# Base_Board.net
KiCad netlist of a schematic drawn in EAGLE
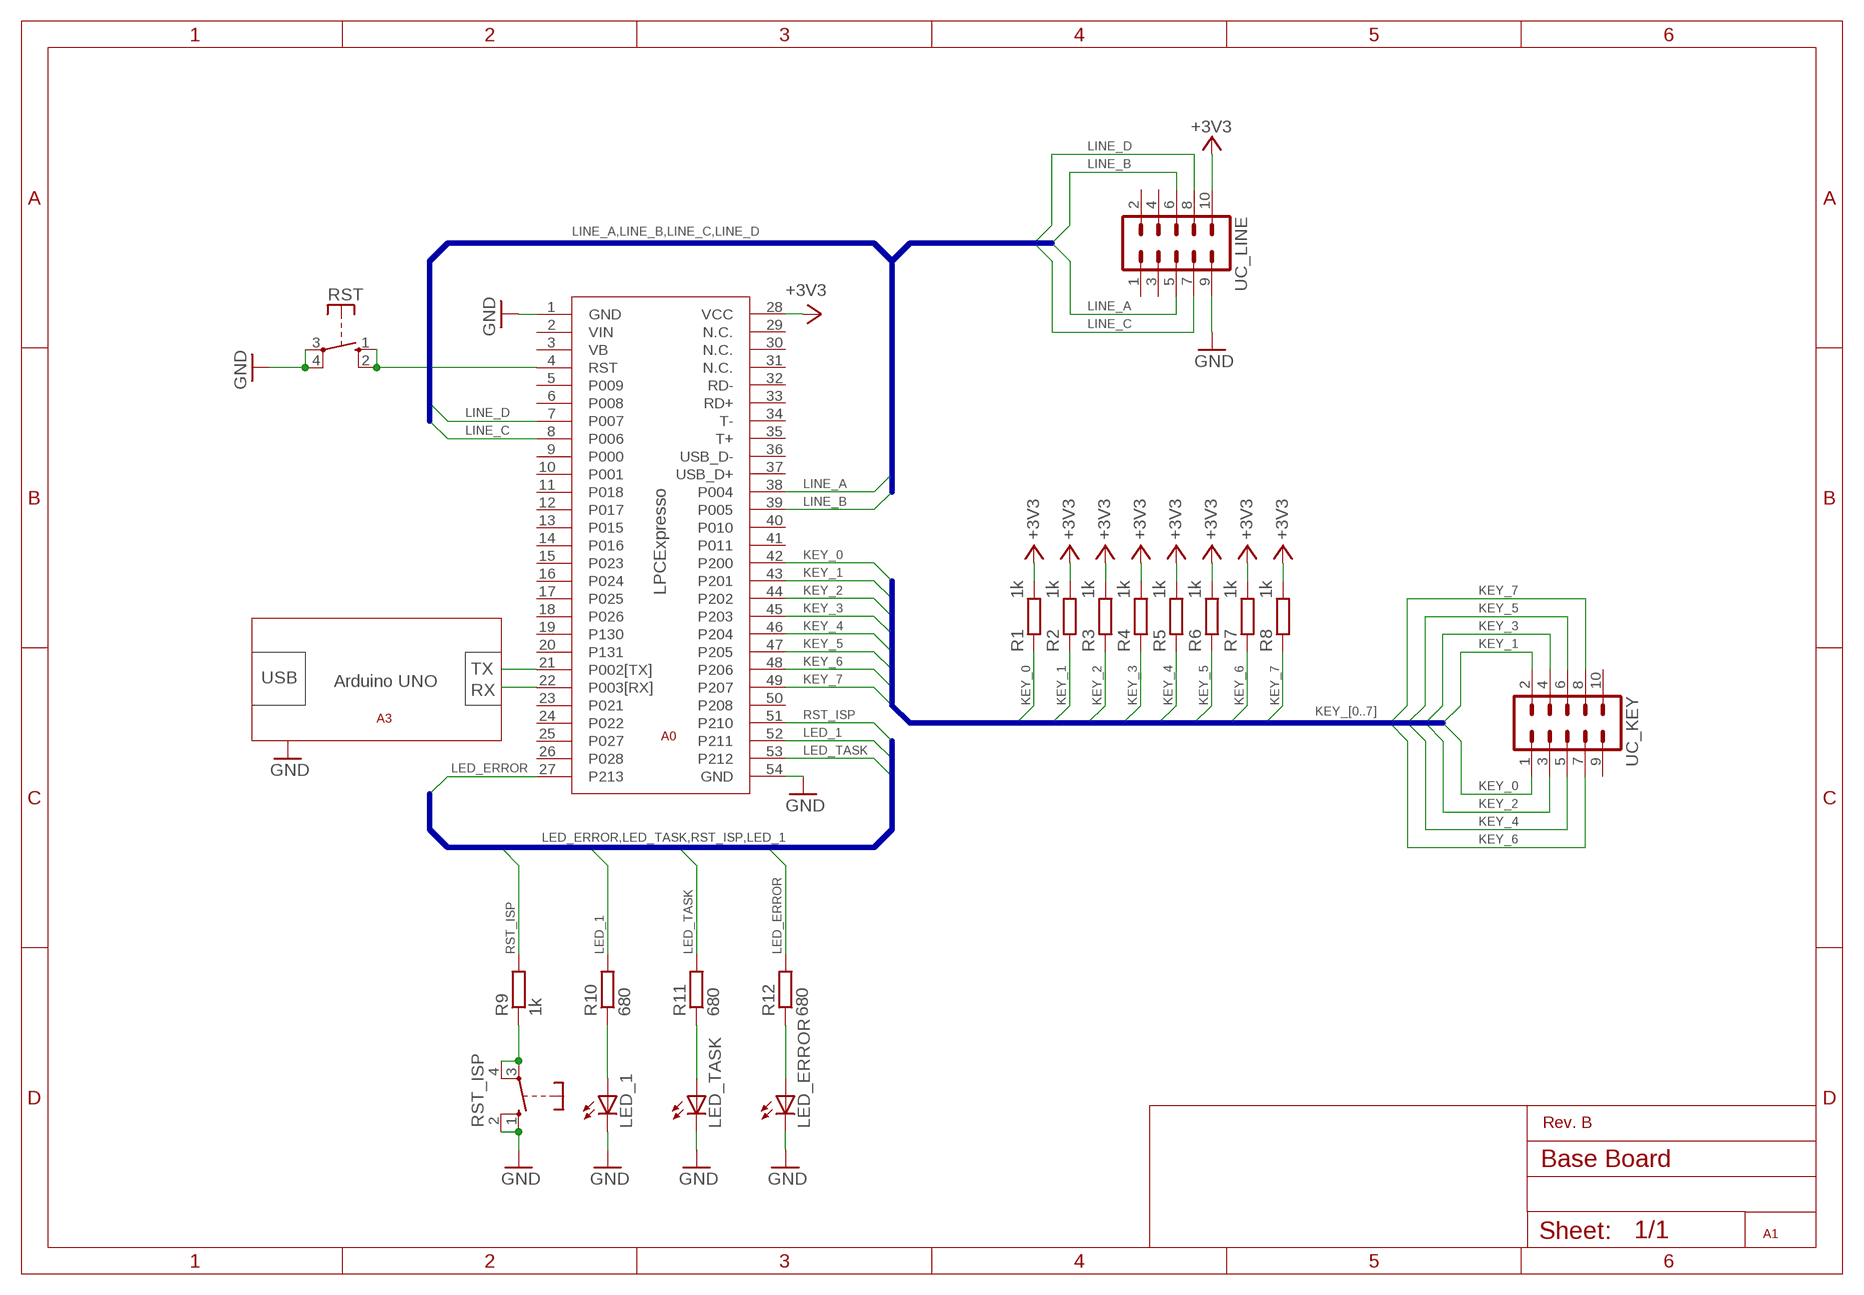
[diagram p0: schematic, sheet 1]

(export (version "E")
  (design (tool "Eeschema 10.0.6"))
  (components
    (comp (ref "LED_1")
      (value "LED5MM")
      (footprint "eagle-import:LED5MM")
      (libsource (lib "eagle-import") (part "LED5MM"))
    )
    (comp (ref "LED_ERROR")
      (value "LED5MM")
      (footprint "eagle-import:LED5MM")
      (libsource (lib "eagle-import") (part "LED5MM"))
    )
    (comp (ref "LED_TASK")
      (value "LED5MM")
      (footprint "eagle-import:LED5MM")
      (libsource (lib "eagle-import") (part "LED5MM"))
    )
    (comp (ref "R1")
      (value "1k")
      (footprint "eagle-import:0204_5")
      (libsource (lib "eagle-import") (part "R-EU_0204/5"))
    )
    (comp (ref "R2")
      (value "1k")
      (footprint "eagle-import:0204_5")
      (libsource (lib "eagle-import") (part "R-EU_0204/5"))
    )
    (comp (ref "R3")
      (value "1k")
      (footprint "eagle-import:0204_5")
      (libsource (lib "eagle-import") (part "R-EU_0204/5"))
    )
    (comp (ref "R4")
      (value "1k")
      (footprint "eagle-import:0204_5")
      (libsource (lib "eagle-import") (part "R-EU_0204/5"))
    )
    (comp (ref "R5")
      (value "1k")
      (footprint "eagle-import:0204_5")
      (libsource (lib "eagle-import") (part "R-EU_0204/5"))
    )
    (comp (ref "R6")
      (value "1k")
      (footprint "eagle-import:0204_5")
      (libsource (lib "eagle-import") (part "R-EU_0204/5"))
    )
    (comp (ref "R7")
      (value "1k")
      (footprint "eagle-import:0204_5")
      (libsource (lib "eagle-import") (part "R-EU_0204/5"))
    )
    (comp (ref "R8")
      (value "1k")
      (footprint "eagle-import:0204_5")
      (libsource (lib "eagle-import") (part "R-EU_0204/5"))
    )
    (comp (ref "R9")
      (value "1k")
      (footprint "eagle-import:0204_5")
      (libsource (lib "eagle-import") (part "R-EU_0204/5"))
    )
    (comp (ref "R10")
      (value "680")
      (footprint "eagle-import:0204_5")
      (libsource (lib "eagle-import") (part "R-EU_0204/5"))
    )
    (comp (ref "R11")
      (value "680")
      (footprint "eagle-import:0204_5")
      (libsource (lib "eagle-import") (part "R-EU_0204/5"))
    )
    (comp (ref "R12")
      (value "680")
      (footprint "eagle-import:0204_5")
      (libsource (lib "eagle-import") (part "R-EU_0204/5"))
    )
    (comp (ref "RST")
      (value "DT6")
      (footprint "eagle-import:DT6")
      (libsource (lib "eagle-import") (part "DT6"))
    )
    (comp (ref "RST_ISP")
      (value "DT6")
      (footprint "eagle-import:DT6")
      (libsource (lib "eagle-import") (part "DT6"))
    )
    (comp (ref "U$1")
      (value "LPCEXPRESSO")
      (footprint "eagle-import:LPCEXPRESSO")
      (libsource (lib "eagle-import") (part "LPCEXPRESSO"))
    )
    (comp (ref "UC_KEY")
      (value "ML10")
      (footprint "eagle-import:ML10")
      (libsource (lib "eagle-import") (part "ML10"))
    )
    (comp (ref "UC_LINE")
      (value "ML10")
      (footprint "eagle-import:ML10")
      (libsource (lib "eagle-import") (part "ML10"))
    )
  )
  (nets
    (net (code "1") (name "+3V3") (class "Default")
      (node (ref "R1") (pin "1") (pinfunction "1_1") (pintype "passive"))
      (node (ref "R2") (pin "1") (pinfunction "1_1") (pintype "passive"))
      (node (ref "R3") (pin "1") (pinfunction "1_1") (pintype "passive"))
      (node (ref "R4") (pin "1") (pinfunction "1_1") (pintype "passive"))
      (node (ref "R5") (pin "1") (pinfunction "1_1") (pintype "passive"))
      (node (ref "R6") (pin "1") (pinfunction "1_1") (pintype "passive"))
      (node (ref "R7") (pin "1") (pinfunction "1_1") (pintype "passive"))
      (node (ref "R8") (pin "1") (pinfunction "1_1") (pintype "passive"))
      (node (ref "U$1") (pin "28") (pinfunction "VCC_28") (pintype "power_in"))
      (node (ref "UC_LINE") (pin "10") (pinfunction "10_10") (pintype "passive"))
    )
    (net (code "2") (name "/KEY_0") (class "Default")
      (node (ref "R1") (pin "2") (pinfunction "2_2") (pintype "passive"))
      (node (ref "U$1") (pin "42") (pinfunction "P200_42") (pintype "bidirectional"))
      (node (ref "UC_KEY") (pin "1") (pinfunction "1_1") (pintype "passive"))
    )
    (net (code "3") (name "/KEY_1") (class "Default")
      (node (ref "R2") (pin "2") (pinfunction "2_2") (pintype "passive"))
      (node (ref "U$1") (pin "43") (pinfunction "P201_43") (pintype "bidirectional"))
      (node (ref "UC_KEY") (pin "2") (pinfunction "2_2") (pintype "passive"))
    )
    (net (code "4") (name "/KEY_2") (class "Default")
      (node (ref "R3") (pin "2") (pinfunction "2_2") (pintype "passive"))
      (node (ref "U$1") (pin "44") (pinfunction "P202_44") (pintype "bidirectional"))
      (node (ref "UC_KEY") (pin "3") (pinfunction "3_3") (pintype "passive"))
    )
    (net (code "5") (name "/KEY_3") (class "Default")
      (node (ref "R4") (pin "2") (pinfunction "2_2") (pintype "passive"))
      (node (ref "U$1") (pin "45") (pinfunction "P203_45") (pintype "bidirectional"))
      (node (ref "UC_KEY") (pin "4") (pinfunction "4_4") (pintype "passive"))
    )
    (net (code "6") (name "/KEY_4") (class "Default")
      (node (ref "R5") (pin "2") (pinfunction "2_2") (pintype "passive"))
      (node (ref "U$1") (pin "46") (pinfunction "P204_46") (pintype "bidirectional"))
      (node (ref "UC_KEY") (pin "5") (pinfunction "5_5") (pintype "passive"))
    )
    (net (code "7") (name "/KEY_5") (class "Default")
      (node (ref "R6") (pin "2") (pinfunction "2_2") (pintype "passive"))
      (node (ref "U$1") (pin "47") (pinfunction "P205_47") (pintype "bidirectional"))
      (node (ref "UC_KEY") (pin "6") (pinfunction "6_6") (pintype "passive"))
    )
    (net (code "8") (name "/KEY_6") (class "Default")
      (node (ref "R7") (pin "2") (pinfunction "2_2") (pintype "passive"))
      (node (ref "U$1") (pin "48") (pinfunction "P206_48") (pintype "bidirectional"))
      (node (ref "UC_KEY") (pin "7") (pinfunction "7_7") (pintype "passive"))
    )
    (net (code "9") (name "/KEY_7") (class "Default")
      (node (ref "R8") (pin "2") (pinfunction "2_2") (pintype "passive"))
      (node (ref "U$1") (pin "49") (pinfunction "P207_49") (pintype "bidirectional"))
      (node (ref "UC_KEY") (pin "8") (pinfunction "8_8") (pintype "passive"))
    )
    (net (code "11") (name "/LED_1") (class "Default")
      (node (ref "R10") (pin "2") (pinfunction "2_2") (pintype "passive"))
      (node (ref "U$1") (pin "52") (pinfunction "P211_52") (pintype "bidirectional"))
    )
    (net (code "12") (name "/LED_ERROR") (class "Default")
      (node (ref "R12") (pin "2") (pinfunction "2_2") (pintype "passive"))
      (node (ref "U$1") (pin "27") (pinfunction "P213_27") (pintype "bidirectional"))
    )
    (net (code "13") (name "/LED_TASK") (class "Default")
      (node (ref "R11") (pin "2") (pinfunction "2_2") (pintype "passive"))
      (node (ref "U$1") (pin "53") (pinfunction "P212_53") (pintype "bidirectional"))
    )
    (net (code "14") (name "/LINE_A") (class "Default")
      (node (ref "U$1") (pin "38") (pinfunction "P004_38") (pintype "bidirectional"))
      (node (ref "UC_LINE") (pin "5") (pinfunction "5_5") (pintype "passive"))
    )
    (net (code "15") (name "/LINE_B") (class "Default")
      (node (ref "U$1") (pin "39") (pinfunction "P005_39") (pintype "bidirectional"))
      (node (ref "UC_LINE") (pin "6") (pinfunction "6_6") (pintype "passive"))
    )
    (net (code "16") (name "/LINE_C") (class "Default")
      (node (ref "U$1") (pin "8") (pinfunction "P006_8") (pintype "bidirectional"))
      (node (ref "UC_LINE") (pin "7") (pinfunction "7_7") (pintype "passive"))
    )
    (net (code "17") (name "/LINE_D") (class "Default")
      (node (ref "U$1") (pin "7") (pinfunction "P007_7") (pintype "bidirectional"))
      (node (ref "UC_LINE") (pin "8") (pinfunction "8_8") (pintype "passive"))
    )
    (net (code "18") (name "/RST_ISP") (class "Default")
      (node (ref "R9") (pin "2") (pinfunction "2_2") (pintype "passive"))
      (node (ref "U$1") (pin "51") (pinfunction "P210_51") (pintype "bidirectional"))
    )
    (net (code "19") (name "/VB") (class "Default")
      (node (ref "U$1") (pin "3") (pinfunction "VB_3") (pintype "power_in"))
    )
    (net (code "22") (name "GND") (class "Default")
      (node (ref "LED_1") (pin "K") (pinfunction "C_K") (pintype "passive"))
      (node (ref "LED_ERROR") (pin "K") (pinfunction "C_K") (pintype "passive"))
      (node (ref "LED_TASK") (pin "K") (pinfunction "C_K") (pintype "passive"))
      (node (ref "RST") (pin "3") (pinfunction "P_3") (pintype "passive"))
      (node (ref "RST") (pin "4") (pinfunction "P_4") (pintype "passive"))
      (node (ref "RST_ISP") (pin "1") (pinfunction "S_1") (pintype "passive"))
      (node (ref "RST_ISP") (pin "2") (pinfunction "S_2") (pintype "passive"))
      (node (ref "U$1") (pin "1") (pinfunction "GND_1") (pintype "power_in"))
      (node (ref "U$1") (pin "54") (pinfunction "GND_54") (pintype "power_in"))
      (node (ref "UC_LINE") (pin "9") (pinfunction "9_9") (pintype "passive"))
    )
    (net (code "23") (name "Net-(LED_1-PadA)") (class "Default")
      (node (ref "LED_1") (pin "A") (pinfunction "A_A") (pintype "passive"))
      (node (ref "R10") (pin "1") (pinfunction "1_1") (pintype "passive"))
    )
    (net (code "24") (name "Net-(LED_ERROR-PadA)") (class "Default")
      (node (ref "LED_ERROR") (pin "A") (pinfunction "A_A") (pintype "passive"))
      (node (ref "R12") (pin "1") (pinfunction "1_1") (pintype "passive"))
    )
    (net (code "25") (name "Net-(LED_TASK-PadA)") (class "Default")
      (node (ref "LED_TASK") (pin "A") (pinfunction "A_A") (pintype "passive"))
      (node (ref "R11") (pin "1") (pinfunction "1_1") (pintype "passive"))
    )
    (net (code "26") (name "Net-(R9-Pad1)") (class "Default")
      (node (ref "R9") (pin "1") (pinfunction "1_1") (pintype "passive"))
      (node (ref "RST_ISP") (pin "3") (pinfunction "P_3") (pintype "passive"))
      (node (ref "RST_ISP") (pin "4") (pinfunction "P_4") (pintype "passive"))
    )
    (net (code "27") (name "Net-(U$1-RST)") (class "Default")
      (node (ref "RST") (pin "1") (pinfunction "S_1") (pintype "passive"))
      (node (ref "RST") (pin "2") (pinfunction "S_2") (pintype "passive"))
      (node (ref "U$1") (pin "4") (pinfunction "RST_4") (pintype "bidirectional"))
    )
    (net (code "28") (name "unconnected-(U$1-N.C.-Pad29)") (class "Default")
      (node (ref "U$1") (pin "29") (pinfunction "N.C._29") (pintype "no_connect"))
    )
    (net (code "29") (name "unconnected-(U$1-N.C.-Pad30)") (class "Default")
      (node (ref "U$1") (pin "30") (pinfunction "N.C._30") (pintype "no_connect"))
    )
    (net (code "30") (name "unconnected-(U$1-N.C.-Pad31)") (class "Default")
      (node (ref "U$1") (pin "31") (pinfunction "N.C._31") (pintype "no_connect"))
    )
    (net (code "31") (name "unconnected-(U$1-P000-Pad9)") (class "Default")
      (node (ref "U$1") (pin "9") (pinfunction "P000_9") (pintype "bidirectional"))
    )
    (net (code "32") (name "unconnected-(U$1-P001-Pad10)") (class "Default")
      (node (ref "U$1") (pin "10") (pinfunction "P001_10") (pintype "bidirectional"))
    )
    (net (code "33") (name "unconnected-(U$1-P002[TX]-Pad21)") (class "Default")
      (node (ref "U$1") (pin "21") (pinfunction "P002[TX]_21") (pintype "bidirectional"))
    )
    (net (code "34") (name "unconnected-(U$1-P003[RX]-Pad22)") (class "Default")
      (node (ref "U$1") (pin "22") (pinfunction "P003[RX]_22") (pintype "bidirectional"))
    )
    (net (code "35") (name "unconnected-(U$1-P008-Pad6)") (class "Default")
      (node (ref "U$1") (pin "6") (pinfunction "P008_6") (pintype "bidirectional"))
    )
    (net (code "36") (name "unconnected-(U$1-P009-Pad5)") (class "Default")
      (node (ref "U$1") (pin "5") (pinfunction "P009_5") (pintype "bidirectional"))
    )
    (net (code "37") (name "unconnected-(U$1-P010-Pad40)") (class "Default")
      (node (ref "U$1") (pin "40") (pinfunction "P010_40") (pintype "bidirectional"))
    )
    (net (code "38") (name "unconnected-(U$1-P011-Pad41)") (class "Default")
      (node (ref "U$1") (pin "41") (pinfunction "P011_41") (pintype "bidirectional"))
    )
    (net (code "39") (name "unconnected-(U$1-P015-Pad13)") (class "Default")
      (node (ref "U$1") (pin "13") (pinfunction "P015_13") (pintype "bidirectional"))
    )
    (net (code "40") (name "unconnected-(U$1-P016-Pad14)") (class "Default")
      (node (ref "U$1") (pin "14") (pinfunction "P016_14") (pintype "bidirectional"))
    )
    (net (code "41") (name "unconnected-(U$1-P017-Pad12)") (class "Default")
      (node (ref "U$1") (pin "12") (pinfunction "P017_12") (pintype "bidirectional"))
    )
    (net (code "42") (name "unconnected-(U$1-P018-Pad11)") (class "Default")
      (node (ref "U$1") (pin "11") (pinfunction "P018_11") (pintype "bidirectional"))
    )
    (net (code "43") (name "unconnected-(U$1-P021-Pad23)") (class "Default")
      (node (ref "U$1") (pin "23") (pinfunction "P021_23") (pintype "bidirectional"))
    )
    (net (code "44") (name "unconnected-(U$1-P022-Pad24)") (class "Default")
      (node (ref "U$1") (pin "24") (pinfunction "P022_24") (pintype "bidirectional"))
    )
    (net (code "45") (name "unconnected-(U$1-P023-Pad15)") (class "Default")
      (node (ref "U$1") (pin "15") (pinfunction "P023_15") (pintype "bidirectional"))
    )
    (net (code "46") (name "unconnected-(U$1-P024-Pad16)") (class "Default")
      (node (ref "U$1") (pin "16") (pinfunction "P024_16") (pintype "bidirectional"))
    )
    (net (code "47") (name "unconnected-(U$1-P025-Pad17)") (class "Default")
      (node (ref "U$1") (pin "17") (pinfunction "P025_17") (pintype "bidirectional"))
    )
    (net (code "48") (name "unconnected-(U$1-P026-Pad18)") (class "Default")
      (node (ref "U$1") (pin "18") (pinfunction "P026_18") (pintype "bidirectional"))
    )
    (net (code "49") (name "unconnected-(U$1-P027-Pad25)") (class "Default")
      (node (ref "U$1") (pin "25") (pinfunction "P027_25") (pintype "bidirectional"))
    )
    (net (code "50") (name "unconnected-(U$1-P028-Pad26)") (class "Default")
      (node (ref "U$1") (pin "26") (pinfunction "P028_26") (pintype "bidirectional"))
    )
    (net (code "51") (name "unconnected-(U$1-P130-Pad19)") (class "Default")
      (node (ref "U$1") (pin "19") (pinfunction "P130_19") (pintype "bidirectional"))
    )
    (net (code "52") (name "unconnected-(U$1-P131-Pad20)") (class "Default")
      (node (ref "U$1") (pin "20") (pinfunction "P131_20") (pintype "bidirectional"))
    )
    (net (code "53") (name "unconnected-(U$1-P208-Pad50)") (class "Default")
      (node (ref "U$1") (pin "50") (pinfunction "P208_50") (pintype "bidirectional"))
    )
    (net (code "54") (name "unconnected-(U$1-RD+-Pad33)") (class "Default")
      (node (ref "U$1") (pin "33") (pinfunction "RD+_33") (pintype "bidirectional"))
    )
    (net (code "55") (name "unconnected-(U$1-RD--Pad32)") (class "Default")
      (node (ref "U$1") (pin "32") (pinfunction "RD-_32") (pintype "bidirectional"))
    )
    (net (code "56") (name "unconnected-(U$1-T+-Pad35)") (class "Default")
      (node (ref "U$1") (pin "35") (pinfunction "T+_35") (pintype "bidirectional"))
    )
    (net (code "57") (name "unconnected-(U$1-T--Pad34)") (class "Default")
      (node (ref "U$1") (pin "34") (pinfunction "T-_34") (pintype "bidirectional"))
    )
    (net (code "58") (name "unconnected-(U$1-USB_D+-Pad37)") (class "Default")
      (node (ref "U$1") (pin "37") (pinfunction "USB_D+_37") (pintype "bidirectional"))
    )
    (net (code "59") (name "unconnected-(U$1-USB_D--Pad36)") (class "Default")
      (node (ref "U$1") (pin "36") (pinfunction "USB_D-_36") (pintype "bidirectional"))
    )
    (net (code "60") (name "unconnected-(U$1-VIN-Pad2)") (class "Default")
      (node (ref "U$1") (pin "2") (pinfunction "VIN_2") (pintype "input"))
    )
    (net (code "61") (name "unconnected-(UC_KEY-Pad9)") (class "Default")
      (node (ref "UC_KEY") (pin "9") (pinfunction "9_9") (pintype "passive"))
    )
    (net (code "62") (name "unconnected-(UC_KEY-Pad10)") (class "Default")
      (node (ref "UC_KEY") (pin "10") (pinfunction "10_10") (pintype "passive"))
    )
    (net (code "63") (name "unconnected-(UC_LINE-Pad1)") (class "Default")
      (node (ref "UC_LINE") (pin "1") (pinfunction "1_1") (pintype "passive"))
    )
    (net (code "64") (name "unconnected-(UC_LINE-Pad2)") (class "Default")
      (node (ref "UC_LINE") (pin "2") (pinfunction "2_2") (pintype "passive"))
    )
    (net (code "65") (name "unconnected-(UC_LINE-Pad3)") (class "Default")
      (node (ref "UC_LINE") (pin "3") (pinfunction "3_3") (pintype "passive"))
    )
    (net (code "66") (name "unconnected-(UC_LINE-Pad4)") (class "Default")
      (node (ref "UC_LINE") (pin "4") (pinfunction "4_4") (pintype "passive"))
    )
  )
)
